# Design_Electronic_Proiect.net
KiCad netlist of a schematic drawn in EAGLE
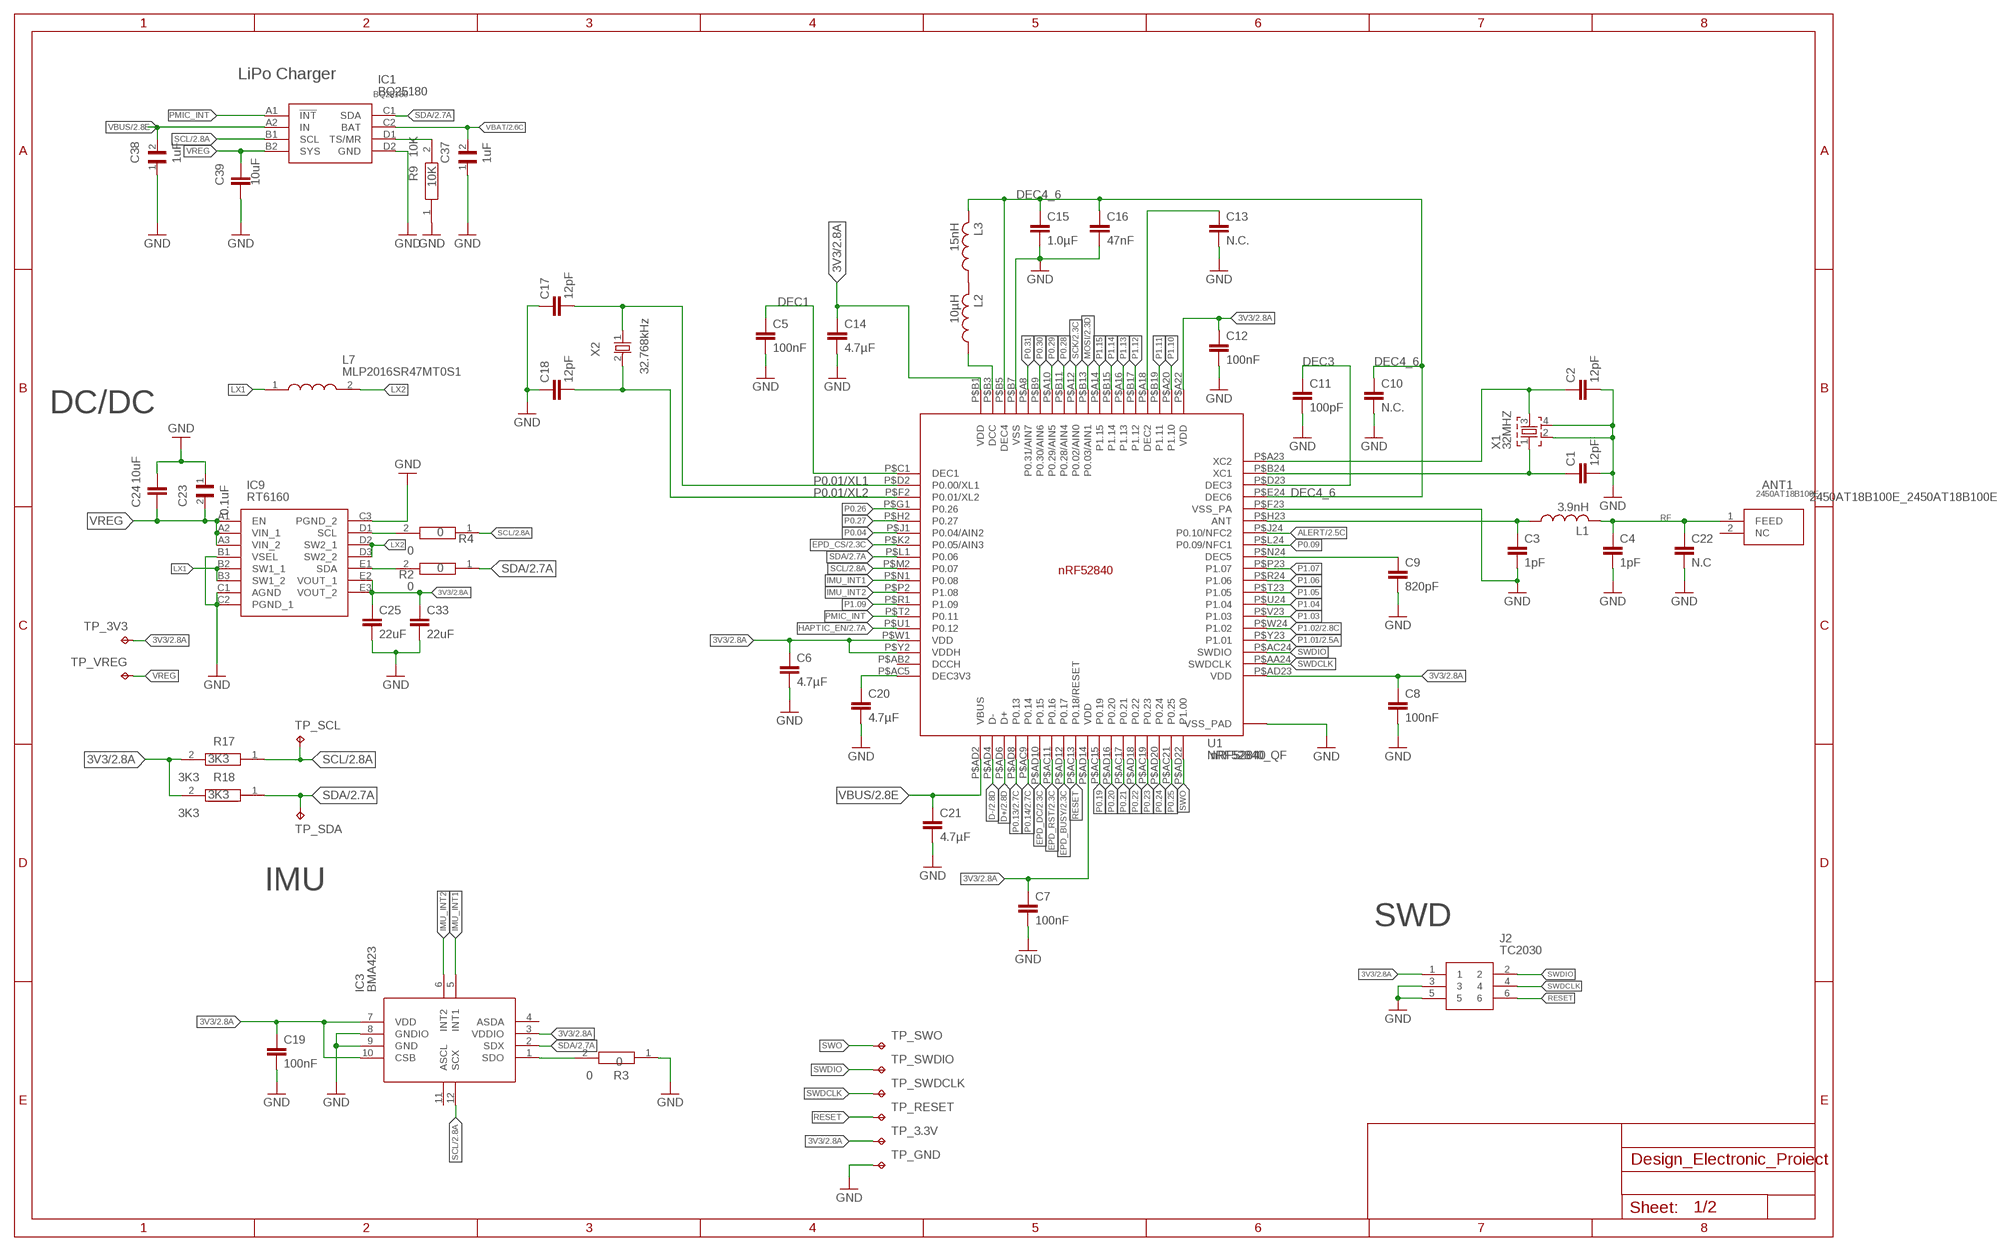
[diagram p0: schematic, sheet 1]
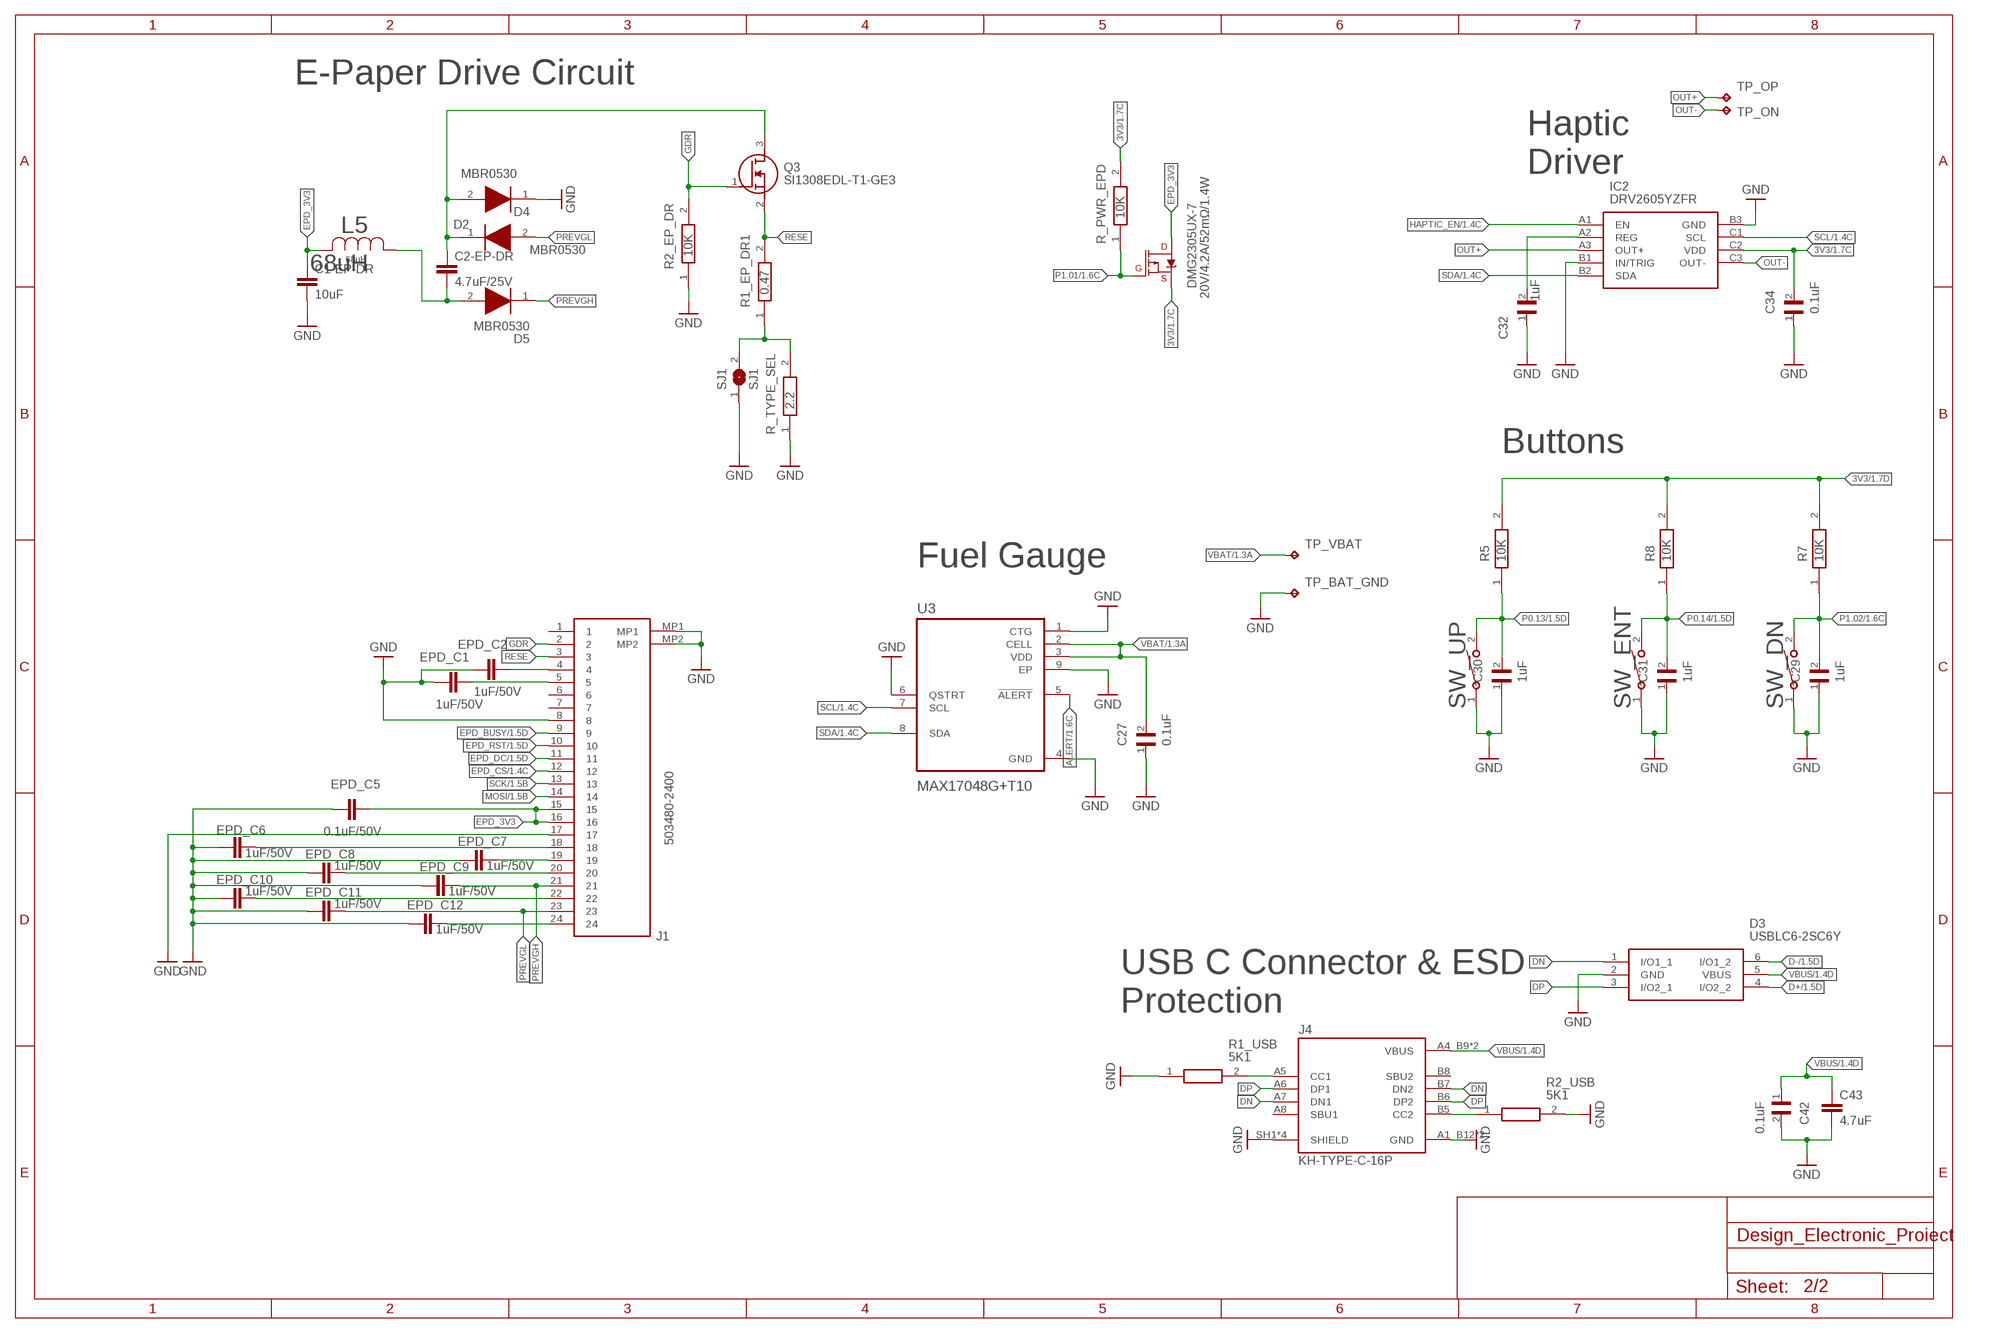
[diagram p1: schematic, sheet 2]

(export (version "E")
  (design (tool "Eeschema 10.0.6"))
  (components
    (comp (ref "ANT1")
      (value "2450AT18B100E_2450AT18B100E")
      (footprint "eagle-import:2450AT18B100E_ANTC3216X140N")
      (fields
        (field (name "ARROW_PART_NUMBER") "2450AT18B100E")
        (field (name "MOUSER_PART_NUMBER") "609-2450AT18B100E")
      )
      (libsource (lib "eagle-import") (part "2450AT18B100E_2450AT18B100E"))
    )
    (comp (ref "C1")
      (value "12pF")
      (footprint "eagle-import:NORDIC_NRF_3_RESC0201_L")
      (libsource (lib "eagle-import") (part "NORDIC_NRF_3_CAPACITOR_0201_L"))
    )
    (comp (ref "C2")
      (value "12pF")
      (footprint "eagle-import:NORDIC_NRF_3_RESC0201_L")
      (libsource (lib "eagle-import") (part "NORDIC_NRF_3_CAPACITOR_0201_L"))
    )
    (comp (ref "C3")
      (value "1pF")
      (footprint "eagle-import:NORDIC_NRF_3_RESC0201_L")
      (libsource (lib "eagle-import") (part "NORDIC_NRF_3_CAPACITOR_0201_L"))
    )
    (comp (ref "C4")
      (value "1pF")
      (footprint "eagle-import:NORDIC_NRF_3_RESC0201_L")
      (libsource (lib "eagle-import") (part "NORDIC_NRF_3_CAPACITOR_0201_L"))
    )
    (comp (ref "C5")
      (value "100nF")
      (footprint "eagle-import:NORDIC_NRF_3_RESC0201_L")
      (libsource (lib "eagle-import") (part "NORDIC_NRF_3_CAPACITOR_0201_L"))
    )
    (comp (ref "C6")
      (value "4.7µF")
      (footprint "eagle-import:NORDIC_NRF_3_RESC0201_L")
      (libsource (lib "eagle-import") (part "NORDIC_NRF_3_CAPACITOR_0201_L"))
    )
    (comp (ref "C7")
      (value "100nF")
      (footprint "eagle-import:NORDIC_NRF_3_RESC0201_L")
      (libsource (lib "eagle-import") (part "NORDIC_NRF_3_CAPACITOR_0201_L"))
    )
    (comp (ref "C8")
      (value "100nF")
      (footprint "eagle-import:NORDIC_NRF_3_RESC0201_L")
      (libsource (lib "eagle-import") (part "NORDIC_NRF_3_CAPACITOR_0201_L"))
    )
    (comp (ref "C9")
      (value "820pF")
      (footprint "eagle-import:NORDIC_NRF_3_RESC0201_L")
      (libsource (lib "eagle-import") (part "NORDIC_NRF_3_CAPACITOR_0201_L"))
    )
    (comp (ref "C10")
      (value "N.C.")
      (footprint "eagle-import:NORDIC_NRF_3_RESC0201_L")
      (libsource (lib "eagle-import") (part "NORDIC_NRF_3_CAPACITOR_0201_L"))
    )
    (comp (ref "C11")
      (value "100pF")
      (footprint "eagle-import:NORDIC_NRF_3_RESC0201_L")
      (libsource (lib "eagle-import") (part "NORDIC_NRF_3_CAPACITOR_0201_L"))
    )
    (comp (ref "C12")
      (value "100nF")
      (footprint "eagle-import:NORDIC_NRF_3_RESC0201_L")
      (libsource (lib "eagle-import") (part "NORDIC_NRF_3_CAPACITOR_0201_L"))
    )
    (comp (ref "C13")
      (value "N.C.")
      (footprint "eagle-import:NORDIC_NRF_3_RESC0201_L")
      (libsource (lib "eagle-import") (part "NORDIC_NRF_3_CAPACITOR_0201_L"))
    )
    (comp (ref "C14")
      (value "4.7µF")
      (footprint "eagle-import:NORDIC_NRF_3_RESC0201_L")
      (libsource (lib "eagle-import") (part "NORDIC_NRF_3_CAPACITOR_0201_L"))
    )
    (comp (ref "C15")
      (value "1.0µF")
      (footprint "eagle-import:NORDIC_NRF_3_RESC0201_L")
      (libsource (lib "eagle-import") (part "NORDIC_NRF_3_CAPACITOR_0201_L"))
    )
    (comp (ref "C16")
      (value "47nF")
      (footprint "eagle-import:NORDIC_NRF_3_RESC0201_L")
      (libsource (lib "eagle-import") (part "NORDIC_NRF_3_CAPACITOR_0201_L"))
    )
    (comp (ref "C17")
      (value "12pF")
      (footprint "eagle-import:NORDIC_NRF_3_RESC0201_L")
      (libsource (lib "eagle-import") (part "NORDIC_NRF_3_CAPACITOR_0201_L"))
    )
    (comp (ref "C18")
      (value "12pF")
      (footprint "eagle-import:NORDIC_NRF_3_RESC0201_L")
      (libsource (lib "eagle-import") (part "NORDIC_NRF_3_CAPACITOR_0201_L"))
    )
    (comp (ref "C19")
      (value "100nF")
      (footprint "eagle-import:NORDIC_NRF_3_RESC0402_L")
      (libsource (lib "eagle-import") (part "NORDIC_NRF_3_CAPACITOR_0402_L"))
    )
    (comp (ref "C20")
      (value "4.7µF")
      (footprint "eagle-import:NORDIC_NRF_3_RESC0201_L")
      (libsource (lib "eagle-import") (part "NORDIC_NRF_3_CAPACITOR_0201_L"))
    )
    (comp (ref "C21")
      (value "4.7µF")
      (footprint "eagle-import:NORDIC_NRF_3_RESC0201_L")
      (libsource (lib "eagle-import") (part "NORDIC_NRF_3_CAPACITOR_0201_L"))
    )
    (comp (ref "C22")
      (value "N.C")
      (footprint "eagle-import:NORDIC_NRF_3_RESC0201_L")
      (libsource (lib "eagle-import") (part "NORDIC_NRF_3_CAPACITOR_0201_L"))
    )
    (comp (ref "C23")
      (value "0.1uF")
      (footprint "eagle-import:GRM011R60J152KE01L_2_CAPC0201X13N")
      (fields (field (name "MF") "Murata") (field (name "MP") "GRM011R60J152KE01L"))
      (libsource (lib "eagle-import") (part "GRM011R60J152KE01L_2_GRM011R60J152KE01L"))
    )
    (comp (ref "C24")
      (value "10uF")
      (footprint "eagle-import:NORDIC_NRF_3_RESC0402_L")
      (libsource (lib "eagle-import") (part "NORDIC_NRF_3_CAPACITOR_0402_L"))
    )
    (comp (ref "C25")
      (value "22uF")
      (footprint "eagle-import:NORDIC_NRF_3_RESC0402_L")
      (libsource (lib "eagle-import") (part "NORDIC_NRF_3_CAPACITOR_0402_L"))
    )
    (comp (ref "C33")
      (value "22uF")
      (footprint "eagle-import:NORDIC_NRF_3_RESC0402_L")
      (libsource (lib "eagle-import") (part "NORDIC_NRF_3_CAPACITOR_0402_L"))
    )
    (comp (ref "C37")
      (value "1uF")
      (footprint "eagle-import:GRM011R60J152KE01L_2_CAPC0201X13N")
      (fields (field (name "MF") "Murata") (field (name "MP") "GRM011R60J152KE01L"))
      (libsource (lib "eagle-import") (part "GRM011R60J152KE01L_2_GRM011R60J152KE01L"))
    )
    (comp (ref "C38")
      (value "1uF")
      (footprint "eagle-import:GRM011R60J152KE01L_2_CAPC0201X13N")
      (fields (field (name "MF") "Murata") (field (name "MP") "GRM011R60J152KE01L"))
      (libsource (lib "eagle-import") (part "GRM011R60J152KE01L_2_GRM011R60J152KE01L"))
    )
    (comp (ref "C39")
      (value "10uF")
      (footprint "eagle-import:NORDIC_NRF_3_RESC0402_L")
      (libsource (lib "eagle-import") (part "NORDIC_NRF_3_CAPACITOR_0402_L"))
    )
    (comp (ref "IC1")
      (value "BQ25180")
      (footprint "eagle-import:BQ25180YBGR_BGA8C40P2X4_100X155X50")
      (fields
        (field (name "ARROW_PART_NUMBER") "BQ25180YBGR")
        (field (name "MOUSER_PART_NUMBER") "595-BQ25180YBGR")
      )
      (libsource (lib "eagle-import") (part "BQ25180YBGR_BQ25180YBGR"))
    )
    (comp (ref "IC3")
      (value "BMA423")
      (footprint "eagle-import:BMA423_BMA423")
      (fields (field (name "MOUSER_PART_NUMBER") "262-BMA423"))
      (libsource (lib "eagle-import") (part "BMA423_BMA423"))
    )
    (comp (ref "IC9")
      (value "RT6160")
      (footprint "eagle-import:RT6160AWSC_BGA15C40P3X5_140X230X60")
      (fields
        (field (name "MANUFACTURER_PART_NUMBER") "RT6160AWSC")
        (field (name "MOUSER_PART_NUMBER") "835-RT6160AWSC")
      )
      (libsource (lib "eagle-import") (part "RT6160AWSC_RT6160AWSC"))
    )
    (comp (ref "J2")
      (value "TC2030")
      (footprint "eagle-import:TC2030-IDC_TC2030IDC")
      (fields (field (name "MANUFACTURER_PART_NUMBER") "TC2030-IDC"))
      (libsource (lib "eagle-import") (part "TC2030-IDC_TC2030-IDC"))
    )
    (comp (ref "L1")
      (value "3.9nH")
      (footprint "eagle-import:NORDIC_NRF_2_RESC0402_L")
      (libsource (lib "eagle-import") (part "NORDIC_NRF_2_INDUCTOR_0402_L"))
    )
    (comp (ref "L2")
      (value "10µH")
      (footprint "eagle-import:NORDIC_NRF_2_RESC0402_L")
      (libsource (lib "eagle-import") (part "NORDIC_NRF_2_INDUCTOR_0402_L"))
    )
    (comp (ref "L3")
      (value "15nH")
      (footprint "eagle-import:NORDIC_NRF_2_RESC0402_L")
      (libsource (lib "eagle-import") (part "NORDIC_NRF_2_INDUCTOR_0402_L"))
    )
    (comp (ref "L7")
      (value "MLP2016SR47MT0S1")
      (footprint "eagle-import:MLP2016SR47MT0S1_INDC2016X100N")
      (fields (field (name "MANUFACTURER_PART_NUMBER") "FTC252012SR47MBCA"))
      (libsource (lib "eagle-import") (part "MLP2016SR47MT0S1_FTC252012SR47MBCA"))
    )
    (comp (ref "R2")
      (value "0")
      (footprint "eagle-import:CPF0201D7K68C1_0201")
      (fields (field (name "R1") "0"))
      (libsource (lib "eagle-import") (part "CPF0201D7K68C1_CPF0201D7K68C1"))
    )
    (comp (ref "R3")
      (value "0")
      (footprint "eagle-import:CPF0201D7K68C1_0201")
      (fields (field (name "R1") "0"))
      (libsource (lib "eagle-import") (part "CPF0201D7K68C1_CPF0201D7K68C1"))
    )
    (comp (ref "R4")
      (value "0")
      (footprint "eagle-import:CPF0201D7K68C1_0201")
      (fields (field (name "R1") "0"))
      (libsource (lib "eagle-import") (part "CPF0201D7K68C1_CPF0201D7K68C1"))
    )
    (comp (ref "R9")
      (value "10K")
      (footprint "eagle-import:CPF0201D7K68C1_0201")
      (fields (field (name "R1") "10K"))
      (libsource (lib "eagle-import") (part "CPF0201D7K68C1_CPF0201D7K68C1"))
    )
    (comp (ref "R17")
      (value "3K3")
      (footprint "eagle-import:CPF0201D7K68C1_0201")
      (fields (field (name "R1") "3K3"))
      (libsource (lib "eagle-import") (part "CPF0201D7K68C1_CPF0201D7K68C1"))
    )
    (comp (ref "R18")
      (value "3K3")
      (footprint "eagle-import:CPF0201D7K68C1_0201")
      (fields (field (name "R1") "3K3"))
      (libsource (lib "eagle-import") (part "CPF0201D7K68C1_CPF0201D7K68C1"))
    )
    (comp (ref "TP_3.3V")
      (value "HECTOR_WATCH_1_TPTP20R")
      (footprint "eagle-import:HECTOR_WATCH_1_TP20R")
      (libsource (lib "eagle-import") (part "HECTOR_WATCH_1_TPTP20R"))
    )
    (comp (ref "TP_3V3")
      (value "HECTOR_WATCH_1_TPTP20R")
      (footprint "eagle-import:HECTOR_WATCH_1_TP20R")
      (libsource (lib "eagle-import") (part "HECTOR_WATCH_1_TPTP20R"))
    )
    (comp (ref "TP_GND")
      (value "HECTOR_WATCH_1_TPTP20R")
      (footprint "eagle-import:HECTOR_WATCH_1_TP20R")
      (libsource (lib "eagle-import") (part "HECTOR_WATCH_1_TPTP20R"))
    )
    (comp (ref "TP_RESET")
      (value "HECTOR_WATCH_1_TPTP20R")
      (footprint "eagle-import:HECTOR_WATCH_1_TP20R")
      (libsource (lib "eagle-import") (part "HECTOR_WATCH_1_TPTP20R"))
    )
    (comp (ref "TP_SCL")
      (value "HECTOR_WATCH_1_TPTP20R")
      (footprint "eagle-import:HECTOR_WATCH_1_TP20R")
      (libsource (lib "eagle-import") (part "HECTOR_WATCH_1_TPTP20R"))
    )
    (comp (ref "TP_SDA")
      (value "HECTOR_WATCH_1_TPTP20R")
      (footprint "eagle-import:HECTOR_WATCH_1_TP20R")
      (libsource (lib "eagle-import") (part "HECTOR_WATCH_1_TPTP20R"))
    )
    (comp (ref "TP_SWDCLK")
      (value "HECTOR_WATCH_1_TPTP20R")
      (footprint "eagle-import:HECTOR_WATCH_1_TP20R")
      (libsource (lib "eagle-import") (part "HECTOR_WATCH_1_TPTP20R"))
    )
    (comp (ref "TP_SWDIO")
      (value "HECTOR_WATCH_1_TPTP20R")
      (footprint "eagle-import:HECTOR_WATCH_1_TP20R")
      (libsource (lib "eagle-import") (part "HECTOR_WATCH_1_TPTP20R"))
    )
    (comp (ref "TP_SWO")
      (value "HECTOR_WATCH_1_TPTP20R")
      (footprint "eagle-import:HECTOR_WATCH_1_TP20R")
      (libsource (lib "eagle-import") (part "HECTOR_WATCH_1_TPTP20R"))
    )
    (comp (ref "TP_VREG")
      (value "HECTOR_WATCH_1_TPTP20R")
      (footprint "eagle-import:HECTOR_WATCH_1_TP20R")
      (libsource (lib "eagle-import") (part "HECTOR_WATCH_1_TPTP20R"))
    )
    (comp (ref "U1")
      (value "nRF52840")
      (footprint "eagle-import:NORDIC_NRF_4_AQFN50P700X700X85_HS-74N")
      (libsource (lib "eagle-import") (part "NORDIC_NRF_4_NRF52840_QF"))
    )
    (comp (ref "X1")
      (value "32MHZ")
      (footprint "eagle-import:NORDIC_NRF_BT-XTAL_2016_N")
      (libsource (lib "eagle-import") (part "NORDIC_NRF_XTAL_32MHZ"))
    )
    (comp (ref "X2")
      (value "32.768kHz")
      (footprint "eagle-import:NORDIC_NRF_1_XTAL_3215_N")
      (libsource (lib "eagle-import") (part "NORDIC_NRF_1_XTAL_32KHZ"))
    )
    (comp (ref "C1-EP-DR")
      (value "10uF")
      (footprint "eagle-import:NORDIC_NRF_3_RESC0402_L")
      (libsource (lib "eagle-import") (part "NORDIC_NRF_3_CAPACITOR_0402_L"))
    )
    (comp (ref "C2-EP-DR")
      (value "4.7uF/25V")
      (footprint "eagle-import:NORDIC_NRF_3_RESC0402_L")
      (libsource (lib "eagle-import") (part "NORDIC_NRF_3_CAPACITOR_0402_L"))
    )
    (comp (ref "C27")
      (value "0.1uF")
      (footprint "eagle-import:GRM011R60J152KE01L_2_CAPC0201X13N")
      (fields (field (name "MF") "Murata") (field (name "MP") "GRM011R60J152KE01L"))
      (libsource (lib "eagle-import") (part "GRM011R60J152KE01L_2_GRM011R60J152KE01L"))
    )
    (comp (ref "C29")
      (value "1uF")
      (footprint "eagle-import:GRM011R60J152KE01L_2_CAPC0201X13N")
      (fields (field (name "MF") "Murata") (field (name "MP") "GRM011R60J152KE01L"))
      (libsource (lib "eagle-import") (part "GRM011R60J152KE01L_2_GRM011R60J152KE01L"))
    )
    (comp (ref "C30")
      (value "1uF")
      (footprint "eagle-import:GRM011R60J152KE01L_2_CAPC0201X13N")
      (fields (field (name "MF") "Murata") (field (name "MP") "GRM011R60J152KE01L"))
      (libsource (lib "eagle-import") (part "GRM011R60J152KE01L_2_GRM011R60J152KE01L"))
    )
    (comp (ref "C31")
      (value "1uF")
      (footprint "eagle-import:GRM011R60J152KE01L_2_CAPC0201X13N")
      (fields (field (name "MF") "Murata") (field (name "MP") "GRM011R60J152KE01L"))
      (libsource (lib "eagle-import") (part "GRM011R60J152KE01L_2_GRM011R60J152KE01L"))
    )
    (comp (ref "C32")
      (value "1uF")
      (footprint "eagle-import:GRM011R60J152KE01L_2_CAPC0201X13N")
      (fields (field (name "MF") "Murata") (field (name "MP") "GRM011R60J152KE01L"))
      (libsource (lib "eagle-import") (part "GRM011R60J152KE01L_2_GRM011R60J152KE01L"))
    )
    (comp (ref "C34")
      (value "0.1uF")
      (footprint "eagle-import:GRM011R60J152KE01L_2_CAPC0201X13N")
      (fields (field (name "MF") "Murata") (field (name "MP") "GRM011R60J152KE01L"))
      (libsource (lib "eagle-import") (part "GRM011R60J152KE01L_2_GRM011R60J152KE01L"))
    )
    (comp (ref "C42")
      (value "0.1uF")
      (footprint "eagle-import:GRM011R60J152KE01L_2_CAPC0201X13N")
      (fields (field (name "MF") "Murata") (field (name "MP") "GRM011R60J152KE01L"))
      (libsource (lib "eagle-import") (part "GRM011R60J152KE01L_2_GRM011R60J152KE01L"))
    )
    (comp (ref "C43")
      (value "4.7uF")
      (footprint "eagle-import:NORDIC_NRF_3_RESC0402_L")
      (libsource (lib "eagle-import") (part "NORDIC_NRF_3_CAPACITOR_0402_L"))
    )
    (comp (ref "D2")
      (value "MBR0530")
      (footprint "eagle-import:ESP32_C6_LIBRARY_5_SOD3716X135N")
      (fields (field (name "MF") "ON Semiconductor"))
      (libsource (lib "eagle-import") (part "ESP32_C6_LIBRARY_5_MBR0530"))
    )
    (comp (ref "D3")
      (value "USBLC6-2SC6Y")
      (footprint "eagle-import:ESP32_C6_LIBRARY_3_SOT95P280X145-6N")
      (fields (field (name "MF") "STMicroelectronics"))
      (libsource (lib "eagle-import") (part "ESP32_C6_LIBRARY_3_USBLC6-2SC6Y"))
    )
    (comp (ref "D4")
      (value "MBR0530")
      (footprint "eagle-import:ESP32_C6_LIBRARY_5_SOD3716X135N")
      (fields (field (name "MF") "ON Semiconductor"))
      (libsource (lib "eagle-import") (part "ESP32_C6_LIBRARY_5_MBR0530"))
    )
    (comp (ref "D5")
      (value "MBR0530")
      (footprint "eagle-import:ESP32_C6_LIBRARY_5_SOD3716X135N")
      (fields (field (name "MF") "ON Semiconductor"))
      (libsource (lib "eagle-import") (part "ESP32_C6_LIBRARY_5_MBR0530"))
    )
    (comp (ref "DMG2305UX-7")
      (value "20V/4.2A/52mΩ/1.4W")
      (footprint "eagle-import:ESP32_C6_LIBRARY_4_ESP32_C6_LIBRARY_4_ESP32_C6_LIBRARY_4_ESP32_C6_LIBRARY_4_ESP32_WROVER_SPARKFUN-DISCRETESEMI_SOT23-3")
      (libsource (lib "eagle-import") (part "ESP32_C6_LIBRARY_4_ESP32_WROVER_SPARKFUN-DISCRETESEMI_MOSFET_PCH-DMG2305UX-7"))
    )
    (comp (ref "EPD_C1")
      (value "1uF/50V")
      (footprint "eagle-import:NORDIC_NRF_3_RESC0402_L")
      (libsource (lib "eagle-import") (part "NORDIC_NRF_3_CAPACITOR_0402_L"))
    )
    (comp (ref "EPD_C2")
      (value "1uF/50V")
      (footprint "eagle-import:NORDIC_NRF_3_RESC0402_L")
      (libsource (lib "eagle-import") (part "NORDIC_NRF_3_CAPACITOR_0402_L"))
    )
    (comp (ref "EPD_C5")
      (value "0.1uF/50V")
      (footprint "eagle-import:NORDIC_NRF_3_RESC0402_L")
      (libsource (lib "eagle-import") (part "NORDIC_NRF_3_CAPACITOR_0402_L"))
    )
    (comp (ref "EPD_C6")
      (value "1uF/50V")
      (footprint "eagle-import:NORDIC_NRF_3_RESC0402_L")
      (libsource (lib "eagle-import") (part "NORDIC_NRF_3_CAPACITOR_0402_L"))
    )
    (comp (ref "EPD_C7")
      (value "1uF/50V")
      (footprint "eagle-import:NORDIC_NRF_3_RESC0402_L")
      (libsource (lib "eagle-import") (part "NORDIC_NRF_3_CAPACITOR_0402_L"))
    )
    (comp (ref "EPD_C8")
      (value "1uF/50V")
      (footprint "eagle-import:NORDIC_NRF_3_RESC0402_L")
      (libsource (lib "eagle-import") (part "NORDIC_NRF_3_CAPACITOR_0402_L"))
    )
    (comp (ref "EPD_C9")
      (value "1uF/50V")
      (footprint "eagle-import:NORDIC_NRF_3_RESC0402_L")
      (libsource (lib "eagle-import") (part "NORDIC_NRF_3_CAPACITOR_0402_L"))
    )
    (comp (ref "EPD_C10")
      (value "1uF/50V")
      (footprint "eagle-import:NORDIC_NRF_3_RESC0402_L")
      (libsource (lib "eagle-import") (part "NORDIC_NRF_3_CAPACITOR_0402_L"))
    )
    (comp (ref "EPD_C11")
      (value "1uF/50V")
      (footprint "eagle-import:NORDIC_NRF_3_RESC0402_L")
      (libsource (lib "eagle-import") (part "NORDIC_NRF_3_CAPACITOR_0402_L"))
    )
    (comp (ref "EPD_C12")
      (value "1uF/50V")
      (footprint "eagle-import:NORDIC_NRF_3_RESC0402_L")
      (libsource (lib "eagle-import") (part "NORDIC_NRF_3_CAPACITOR_0402_L"))
    )
    (comp (ref "IC2")
      (value "DRV2605YZFR")
      (footprint "eagle-import:DRV2605YZFR_BGA9C50P3X3_144X144X62")
      (libsource (lib "eagle-import") (part "DRV2605YZFR_DRV2605YZFR"))
    )
    (comp (ref "J1")
      (value "503480-2400")
      (footprint "eagle-import:503480-2400_5034802400")
      (fields (field (name "MOUSER_PART_NUMBER") "538-503480-2400"))
      (libsource (lib "eagle-import") (part "503480-2400_503480-2400"))
    )
    (comp (ref "J4")
      (value "KH-TYPE-C-16P")
      (footprint "eagle-import:KH-TYPE-C-16P_KINGHELM_KH-TYPE-C-16P")
      (fields (field (name "MF") "kinghelm"))
      (libsource (lib "eagle-import") (part "KH-TYPE-C-16P_KH-TYPE-C-16P"))
    )
    (comp (ref "L5")
      (value "68uH")
      (footprint "eagle-import:ESP32_C6_LIBRARY_2_IND_4828-WE-TPC_WRE")
      (fields
        (field (name "MANUFACTURER_PART_NUMBER") "744043680")
        (field (name "SHOW_VALUE") "68uH")
        (field (name "COPYRIGHT") "Copyright (C) 2024 Ultra Librarian. All rights reserved.")
      )
      (libsource (lib "eagle-import") (part "ESP32_C6_LIBRARY_2_744043680IND_4828-WE-TPC_WRE"))
    )
    (comp (ref "Q3")
      (value "SI1308EDL-T1-GE3")
      (footprint "eagle-import:ESP32_C6_LIBRARY_6_SOT65P210X110-3N")
      (fields (field (name "MF") "Vishay Siliconix"))
      (libsource (lib "eagle-import") (part "ESP32_C6_LIBRARY_6_SI1308EDL-T1-GE3"))
    )
    (comp (ref "R1_EP_DR1")
      (value "0.47")
      (footprint "eagle-import:CPF0201D7K68C1_0201")
      (libsource (lib "eagle-import") (part "CPF0201D7K68C1_CPF0201D7K68C1"))
    )
    (comp (ref "R1_USB")
      (value "5K1")
      (footprint "eagle-import:CPF0201D7K68C1_0201")
      (libsource (lib "eagle-import") (part "CPF0201D7K68C1_CPF0201D7K68C1"))
    )
    (comp (ref "R2_EP_DR")
      (value "10K")
      (footprint "eagle-import:CPF0201D7K68C1_0201")
      (libsource (lib "eagle-import") (part "CPF0201D7K68C1_CPF0201D7K68C1"))
    )
    (comp (ref "R2_USB")
      (value "5K1")
      (footprint "eagle-import:CPF0201D7K68C1_0201")
      (libsource (lib "eagle-import") (part "CPF0201D7K68C1_CPF0201D7K68C1"))
    )
    (comp (ref "R5")
      (value "10K")
      (footprint "eagle-import:CPF0201D7K68C1_0201")
      (libsource (lib "eagle-import") (part "CPF0201D7K68C1_CPF0201D7K68C1"))
    )
    (comp (ref "R7")
      (value "10K")
      (footprint "eagle-import:CPF0201D7K68C1_0201")
      (libsource (lib "eagle-import") (part "CPF0201D7K68C1_CPF0201D7K68C1"))
    )
    (comp (ref "R8")
      (value "10K")
      (footprint "eagle-import:CPF0201D7K68C1_0201")
      (libsource (lib "eagle-import") (part "CPF0201D7K68C1_CPF0201D7K68C1"))
    )
    (comp (ref "R_PWR_EPD")
      (value "10K")
      (footprint "eagle-import:CPF0201D7K68C1_0201")
      (libsource (lib "eagle-import") (part "CPF0201D7K68C1_CPF0201D7K68C1"))
    )
    (comp (ref "R_TYPE_SEL")
      (value "2.2")
      (footprint "eagle-import:CPF0201D7K68C1_0201")
      (libsource (lib "eagle-import") (part "CPF0201D7K68C1_CPF0201D7K68C1"))
    )
    (comp (ref "SJ1")
      (value "SJ1")
      (footprint "eagle-import:ESP32_C6_LIBRARY_7_JUMPER_SJ")
      (libsource (lib "eagle-import") (part "ESP32_C6_LIBRARY_7_JUMPER_SJ"))
    )
    (comp (ref "SW_DN")
      (value "2025-10-22_07-23-44_LIBRARY_EVP-AKE31ASW_EVP-AKE31A_PAN")
      (footprint "eagle-import:2025-10-22_07-23-44_LIBRARY_SW_EVP-AKE31A_PAN")
      (fields
        (field (name "MANUFACTURER_PART_NUMBER") "EVP-AKE31A")
        (field (name "COPYRIGHT") "Copyright (C) 2025 Ultra Librarian. All rights reserved.")
      )
      (libsource (lib "eagle-import") (part "2025-10-22_07-23-44_LIBRARY_EVP-AKE31ASW_EVP-AKE31A_PAN"))
    )
    (comp (ref "SW_ENT")
      (value "2025-10-22_07-23-44_LIBRARY_EVP-AKE31ASW_EVP-AKE31A_PAN")
      (footprint "eagle-import:2025-10-22_07-23-44_LIBRARY_SW_EVP-AKE31A_PAN")
      (fields
        (field (name "MANUFACTURER_PART_NUMBER") "EVP-AKE31A")
        (field (name "COPYRIGHT") "Copyright (C) 2025 Ultra Librarian. All rights reserved.")
      )
      (libsource (lib "eagle-import") (part "2025-10-22_07-23-44_LIBRARY_EVP-AKE31ASW_EVP-AKE31A_PAN"))
    )
    (comp (ref "SW_UP")
      (value "2025-10-22_07-23-44_LIBRARY_EVP-AKE31ASW_EVP-AKE31A_PAN")
      (footprint "eagle-import:2025-10-22_07-23-44_LIBRARY_SW_EVP-AKE31A_PAN")
      (fields
        (field (name "MANUFACTURER_PART_NUMBER") "EVP-AKE31A")
        (field (name "COPYRIGHT") "Copyright (C) 2025 Ultra Librarian. All rights reserved.")
      )
      (libsource (lib "eagle-import") (part "2025-10-22_07-23-44_LIBRARY_EVP-AKE31ASW_EVP-AKE31A_PAN"))
    )
    (comp (ref "TP_BAT_GND")
      (value "HECTOR_WATCH_1_TPTP20R")
      (footprint "eagle-import:HECTOR_WATCH_1_TP20R")
      (libsource (lib "eagle-import") (part "HECTOR_WATCH_1_TPTP20R"))
    )
    (comp (ref "TP_ON")
      (value "HECTOR_WATCH_1_TPTP20R")
      (footprint "eagle-import:HECTOR_WATCH_1_TP20R")
      (libsource (lib "eagle-import") (part "HECTOR_WATCH_1_TPTP20R"))
    )
    (comp (ref "TP_OP")
      (value "HECTOR_WATCH_1_TPTP20R")
      (footprint "eagle-import:HECTOR_WATCH_1_TP20R")
      (libsource (lib "eagle-import") (part "HECTOR_WATCH_1_TPTP20R"))
    )
    (comp (ref "TP_VBAT")
      (value "HECTOR_WATCH_1_TPTP20R")
      (footprint "eagle-import:HECTOR_WATCH_1_TP20R")
      (libsource (lib "eagle-import") (part "HECTOR_WATCH_1_TPTP20R"))
    )
    (comp (ref "U3")
      (value "MAX17048G+T10")
      (footprint "eagle-import:ESP32_C6_LIBRARY_SON50P200X200X80-9N")
      (fields (field (name "MF") "Analog Devices"))
      (libsource (lib "eagle-import") (part "ESP32_C6_LIBRARY_MAX17048G+T10"))
    )
  )
  (nets
    (net (code "1") (name "3V3") (class "Default")
      (node (ref "C12") (pin "1") (pinfunction "1_1") (pintype "passive"))
      (node (ref "C14") (pin "1") (pinfunction "1_1") (pintype "passive"))
      (node (ref "C19") (pin "1") (pinfunction "1_1") (pintype "passive"))
      (node (ref "C25") (pin "1") (pinfunction "1_1") (pintype "passive"))
      (node (ref "C33") (pin "1") (pinfunction "1_1") (pintype "passive"))
      (node (ref "C34") (pin "2") (pinfunction "2_2") (pintype "passive"))
      (node (ref "C6") (pin "1") (pinfunction "1_1") (pintype "passive"))
      (node (ref "C7") (pin "1") (pinfunction "1_1") (pintype "passive"))
      (node (ref "C8") (pin "1") (pinfunction "1_1") (pintype "passive"))
      (node (ref "DMG2305UX-7") (pin "2") (pinfunction "S_2") (pintype "bidirectional"))
      (node (ref "IC2") (pin "C2") (pinfunction "VDD_C2") (pintype "bidirectional"))
      (node (ref "IC3") (pin "10") (pinfunction "CSB_10") (pintype "bidirectional"))
      (node (ref "IC3") (pin "3") (pinfunction "VDDIO_3") (pintype "bidirectional"))
      (node (ref "IC3") (pin "7") (pinfunction "VDD_7") (pintype "bidirectional"))
      (node (ref "IC9") (pin "E2") (pinfunction "VOUT_1_E2") (pintype "bidirectional"))
      (node (ref "IC9") (pin "E3") (pinfunction "VOUT_2_E3") (pintype "bidirectional"))
      (node (ref "J2") (pin "1") (pinfunction "1_1") (pintype "bidirectional"))
      (node (ref "R17") (pin "2") (pinfunction "2_2") (pintype "bidirectional"))
      (node (ref "R18") (pin "2") (pinfunction "2_2") (pintype "bidirectional"))
      (node (ref "R_PWR_EPD") (pin "2") (pinfunction "2_2") (pintype "bidirectional"))
      (node (ref "TP_3.3V") (pin "TP") (pinfunction "TP_TP") (pintype "input"))
      (node (ref "TP_3V3") (pin "TP") (pinfunction "TP_TP") (pintype "input"))
      (node (ref "U1") (pin "P$A22") (pinfunction "VDD_P$A22") (pintype "power_in"))
      (node (ref "U1") (pin "P$AD14") (pinfunction "VDD_P$AD14") (pintype "power_in"))
      (node (ref "U1") (pin "P$AD23") (pinfunction "VDD_P$AD23") (pintype "power_in"))
      (node (ref "U1") (pin "P$B1") (pinfunction "VDD_P$B1") (pintype "power_in"))
      (node (ref "U1") (pin "P$W1") (pinfunction "VDD_P$W1") (pintype "power_in"))
      (node (ref "U1") (pin "P$Y2") (pinfunction "VDDH_P$Y2") (pintype "power_in"))
    )
    (net (code "2") (name "3V3{slash}1.7D") (class "Default")
      (node (ref "R5") (pin "2") (pinfunction "2_2") (pintype "bidirectional"))
      (node (ref "R7") (pin "2") (pinfunction "2_2") (pintype "bidirectional"))
      (node (ref "R8") (pin "2") (pinfunction "2_2") (pintype "bidirectional"))
    )
    (net (code "3") (name "ALERT") (class "Default")
      (node (ref "U1") (pin "P$J24") (pinfunction "P0.10/NFC2_P$J24") (pintype "bidirectional"))
      (node (ref "U3") (pin "5") (pinfunction "~{ALERT}_5") (pintype "output"))
    )
    (net (code "4") (name "D+") (class "Default")
      (node (ref "D3") (pin "4") (pinfunction "I/O2_2_4") (pintype "bidirectional"))
      (node (ref "U1") (pin "P$AD6") (pinfunction "D+_P$AD6") (pintype "bidirectional"))
    )
    (net (code "5") (name "D-") (class "Default")
      (node (ref "D3") (pin "6") (pinfunction "I/O1_2_6") (pintype "bidirectional"))
      (node (ref "U1") (pin "P$AD4") (pinfunction "D-_P$AD4") (pintype "bidirectional"))
    )
    (net (code "6") (name "DEC1") (class "Default")
      (node (ref "C5") (pin "1") (pinfunction "1_1") (pintype "passive"))
      (node (ref "U1") (pin "P$C1") (pinfunction "DEC1_P$C1") (pintype "power_in"))
    )
    (net (code "7") (name "DEC3") (class "Default")
      (node (ref "C11") (pin "1") (pinfunction "1_1") (pintype "passive"))
      (node (ref "U1") (pin "P$D23") (pinfunction "DEC3_P$D23") (pintype "bidirectional"))
    )
    (net (code "8") (name "DEC4_6") (class "Default")
      (node (ref "C10") (pin "1") (pinfunction "1_1") (pintype "passive"))
      (node (ref "C15") (pin "1") (pinfunction "1_1") (pintype "passive"))
      (node (ref "C16") (pin "1") (pinfunction "1_1") (pintype "passive"))
      (node (ref "L3") (pin "2") (pinfunction "2_2") (pintype "passive"))
      (node (ref "U1") (pin "P$B5") (pinfunction "DEC4_P$B5") (pintype "power_in"))
      (node (ref "U1") (pin "P$E24") (pinfunction "DEC6_P$E24") (pintype "bidirectional"))
    )
    (net (code "9") (name "DN") (class "Default")
      (node (ref "D3") (pin "1") (pinfunction "I/O1_1_1") (pintype "bidirectional"))
      (node (ref "J4") (pin "A7") (pinfunction "DN1_A7") (pintype "bidirectional"))
      (node (ref "J4") (pin "B7") (pinfunction "DN2_B7") (pintype "bidirectional"))
    )
    (net (code "10") (name "DP") (class "Default")
      (node (ref "D3") (pin "3") (pinfunction "I/O2_1_3") (pintype "bidirectional"))
      (node (ref "J4") (pin "A6") (pinfunction "DP1_A6") (pintype "bidirectional"))
      (node (ref "J4") (pin "B6") (pinfunction "DP2_B6") (pintype "bidirectional"))
    )
    (net (code "11") (name "EPD_3V3") (class "Default")
      (node (ref "C1-EP-DR") (pin "1") (pinfunction "1_1") (pintype "passive"))
      (node (ref "DMG2305UX-7") (pin "3") (pinfunction "D_3") (pintype "bidirectional"))
      (node (ref "EPD_C5") (pin "2") (pinfunction "2_2") (pintype "passive"))
      (node (ref "J1") (pin "15") (pinfunction "15_15") (pintype "bidirectional"))
      (node (ref "J1") (pin "16") (pinfunction "16_16") (pintype "bidirectional"))
      (node (ref "L5") (pin "2") (pinfunction "2_2") (pintype "passive"))
    )
    (net (code "12") (name "EPD_BUSY") (class "Default")
      (node (ref "J1") (pin "9") (pinfunction "9_9") (pintype "bidirectional"))
      (node (ref "U1") (pin "P$AD12") (pinfunction "P0.17_P$AD12") (pintype "bidirectional"))
    )
    (net (code "13") (name "EPD_CS") (class "Default")
      (node (ref "J1") (pin "12") (pinfunction "12_12") (pintype "bidirectional"))
      (node (ref "U1") (pin "P$K2") (pinfunction "P0.05/AIN3_P$K2") (pintype "bidirectional"))
    )
    (net (code "14") (name "EPD_DC") (class "Default")
      (node (ref "J1") (pin "11") (pinfunction "11_11") (pintype "bidirectional"))
      (node (ref "U1") (pin "P$AD10") (pinfunction "P0.15_P$AD10") (pintype "bidirectional"))
    )
    (net (code "15") (name "EPD_RST") (class "Default")
      (node (ref "J1") (pin "10") (pinfunction "10_10") (pintype "bidirectional"))
      (node (ref "U1") (pin "P$AC11") (pinfunction "P0.16_P$AC11") (pintype "bidirectional"))
    )
    (net (code "16") (name "GDR") (class "Default")
      (node (ref "J1") (pin "2") (pinfunction "2_2") (pintype "bidirectional"))
      (node (ref "Q3") (pin "1") (pinfunction "G_1") (pintype "bidirectional"))
      (node (ref "R2_EP_DR") (pin "2") (pinfunction "2_2") (pintype "bidirectional"))
    )
    (net (code "17") (name "GND") (class "Default")
      (node (ref "C1") (pin "2") (pinfunction "2_2") (pintype "passive"))
      (node (ref "C1-EP-DR") (pin "2") (pinfunction "2_2") (pintype "passive"))
      (node (ref "C10") (pin "2") (pinfunction "2_2") (pintype "passive"))
      (node (ref "C11") (pin "2") (pinfunction "2_2") (pintype "passive"))
      (node (ref "C12") (pin "2") (pinfunction "2_2") (pintype "passive"))
      (node (ref "C13") (pin "2") (pinfunction "2_2") (pintype "passive"))
      (node (ref "C14") (pin "2") (pinfunction "2_2") (pintype "passive"))
      (node (ref "C15") (pin "2") (pinfunction "2_2") (pintype "passive"))
      (node (ref "C16") (pin "2") (pinfunction "2_2") (pintype "passive"))
      (node (ref "C17") (pin "1") (pinfunction "1_1") (pintype "passive"))
      (node (ref "C18") (pin "1") (pinfunction "1_1") (pintype "passive"))
      (node (ref "C19") (pin "2") (pinfunction "2_2") (pintype "passive"))
      (node (ref "C2") (pin "2") (pinfunction "2_2") (pintype "passive"))
      (node (ref "C20") (pin "2") (pinfunction "2_2") (pintype "passive"))
      (node (ref "C21") (pin "2") (pinfunction "2_2") (pintype "passive"))
      (node (ref "C22") (pin "2") (pinfunction "2_2") (pintype "passive"))
      (node (ref "C23") (pin "1") (pinfunction "1_1") (pintype "passive"))
      (node (ref "C24") (pin "1") (pinfunction "1_1") (pintype "passive"))
      (node (ref "C25") (pin "2") (pinfunction "2_2") (pintype "passive"))
      (node (ref "C27") (pin "1") (pinfunction "1_1") (pintype "passive"))
      (node (ref "C29") (pin "1") (pinfunction "1_1") (pintype "passive"))
      (node (ref "C3") (pin "2") (pinfunction "2_2") (pintype "passive"))
      (node (ref "C30") (pin "1") (pinfunction "1_1") (pintype "passive"))
      (node (ref "C31") (pin "1") (pinfunction "1_1") (pintype "passive"))
      (node (ref "C32") (pin "1") (pinfunction "1_1") (pintype "passive"))
      (node (ref "C33") (pin "2") (pinfunction "2_2") (pintype "passive"))
      (node (ref "C34") (pin "1") (pinfunction "1_1") (pintype "passive"))
      (node (ref "C37") (pin "1") (pinfunction "1_1") (pintype "passive"))
      (node (ref "C38") (pin "1") (pinfunction "1_1") (pintype "passive"))
      (node (ref "C39") (pin "2") (pinfunction "2_2") (pintype "passive"))
      (node (ref "C4") (pin "2") (pinfunction "2_2") (pintype "passive"))
      (node (ref "C42") (pin "2") (pinfunction "2_2") (pintype "passive"))
      (node (ref "C43") (pin "2") (pinfunction "2_2") (pintype "passive"))
      (node (ref "C5") (pin "2") (pinfunction "2_2") (pintype "passive"))
      (node (ref "C6") (pin "2") (pinfunction "2_2") (pintype "passive"))
      (node (ref "C7") (pin "2") (pinfunction "2_2") (pintype "passive"))
      (node (ref "C8") (pin "2") (pinfunction "2_2") (pintype "passive"))
      (node (ref "C9") (pin "2") (pinfunction "2_2") (pintype "passive"))
      (node (ref "D3") (pin "2") (pinfunction "GND_2") (pintype "bidirectional"))
      (node (ref "D4") (pin "1") (pinfunction "K_1") (pintype "bidirectional"))
      (node (ref "EPD_C1") (pin "1") (pinfunction "1_1") (pintype "passive"))
      (node (ref "EPD_C10") (pin "1") (pinfunction "1_1") (pintype "passive"))
      (node (ref "EPD_C11") (pin "1") (pinfunction "1_1") (pintype "passive"))
      (node (ref "EPD_C12") (pin "1") (pinfunction "1_1") (pintype "passive"))
      (node (ref "EPD_C2") (pin "1") (pinfunction "1_1") (pintype "passive"))
      (node (ref "EPD_C5") (pin "1") (pinfunction "1_1") (pintype "passive"))
      (node (ref "EPD_C6") (pin "1") (pinfunction "1_1") (pintype "passive"))
      (node (ref "EPD_C7") (pin "1") (pinfunction "1_1") (pintype "passive"))
      (node (ref "EPD_C8") (pin "1") (pinfunction "1_1") (pintype "passive"))
      (node (ref "EPD_C9") (pin "1") (pinfunction "1_1") (pintype "passive"))
      (node (ref "IC1") (pin "D2") (pinfunction "GND_D2") (pintype "bidirectional"))
      (node (ref "IC2") (pin "B1") (pinfunction "IN/TRIG_B1") (pintype "bidirectional"))
      (node (ref "IC2") (pin "B3") (pinfunction "GND_B3") (pintype "bidirectional"))
      (node (ref "IC3") (pin "8") (pinfunction "GNDIO_8") (pintype "bidirectional"))
      (node (ref "IC3") (pin "9") (pinfunction "GND_9") (pintype "bidirectional"))
      (node (ref "IC9") (pin "B1") (pinfunction "VSEL_B1") (pintype "bidirectional"))
      (node (ref "IC9") (pin "C1") (pinfunction "AGND_C1") (pintype "bidirectional"))
      (node (ref "IC9") (pin "C2") (pinfunction "PGND_1_C2") (pintype "bidirectional"))
      (node (ref "IC9") (pin "C3") (pinfunction "PGND_2_C3") (pintype "bidirectional"))
      (node (ref "J1") (pin "17") (pinfunction "17_17") (pintype "bidirectional"))
      (node (ref "J1") (pin "8") (pinfunction "8_8") (pintype "bidirectional"))
      (node (ref "J1") (pin "MP1") (pinfunction "MP1_MP1") (pintype "bidirectional"))
      (node (ref "J1") (pin "MP2") (pinfunction "MP2_MP2") (pintype "bidirectional"))
      (node (ref "J2") (pin "3") (pinfunction "3_3") (pintype "bidirectional"))
      (node (ref "J2") (pin "5") (pinfunction "5_5") (pintype "bidirectional"))
      (node (ref "J4") (pin "A12_B1") (pinfunction "GND_A12_B1") (pintype "power_in"))
      (node (ref "J4") (pin "A1_B12") (pinfunction "GND_A1_B12") (pintype "power_in"))
      (node (ref "J4") (pin "SH1") (pinfunction "SHIELD_SH1") (pintype "passive"))
      (node (ref "J4") (pin "SH2") (pinfunction "SHIELD_SH2") (pintype "passive"))
      (node (ref "J4") (pin "SH3") (pinfunction "SHIELD_SH3") (pintype "passive"))
      (node (ref "J4") (pin "SH4") (pinfunction "SHIELD_SH4") (pintype "passive"))
      (node (ref "R1_USB") (pin "1") (pinfunction "1_1") (pintype "bidirectional"))
      (node (ref "R2_EP_DR") (pin "1") (pinfunction "1_1") (pintype "bidirectional"))
      (node (ref "R2_USB") (pin "2") (pinfunction "2_2") (pintype "bidirectional"))
      (node (ref "R3") (pin "1") (pinfunction "1_1") (pintype "bidirectional"))
      (node (ref "R9") (pin "1") (pinfunction "1_1") (pintype "bidirectional"))
      (node (ref "R_TYPE_SEL") (pin "1") (pinfunction "1_1") (pintype "bidirectional"))
      (node (ref "SJ1") (pin "1") (pinfunction "1_1") (pintype "passive"))
      (node (ref "SW_DN") (pin "1") (pinfunction "1_1") (pintype "passive"))
      (node (ref "SW_ENT") (pin "1") (pinfunction "1_1") (pintype "passive"))
      (node (ref "SW_UP") (pin "1") (pinfunction "1_1") (pintype "passive"))
      (node (ref "TP_BAT_GND") (pin "TP") (pinfunction "TP_TP") (pintype "input"))
      (node (ref "TP_GND") (pin "TP") (pinfunction "TP_TP") (pintype "input"))
      (node (ref "U1") (pin "P$74") (pinfunction "VSS_PAD_P$74") (pintype "bidirectional"))
      (node (ref "U1") (pin "P$75") (pinfunction "VSS_PAD_P$75") (pintype "bidirectional"))
      (node (ref "U1") (pin "P$76") (pinfunction "VSS_PAD_P$76") (pintype "bidirectional"))
      (node (ref "U1") (pin "P$77") (pinfunction "VSS_PAD_P$77") (pintype "bidirectional"))
      (node (ref "U1") (pin "P$78") (pinfunction "VSS_PAD_P$78") (pintype "bidirectional"))
      (node (ref "U1") (pin "P$79") (pinfunction "VSS_PAD_P$79") (pintype "bidirectional"))
      (node (ref "U1") (pin "P$80") (pinfunction "VSS_PAD_P$80") (pintype "bidirectional"))
      (node (ref "U1") (pin "P$81") (pinfunction "VSS_PAD_P$81") (pintype "bidirectional"))
      (node (ref "U1") (pin "P$82") (pinfunction "VSS_PAD_P$82") (pintype "bidirectional"))
      (node (ref "U1") (pin "P$83") (pinfunction "VSS_PAD_P$83") (pintype "bidirectional"))
      (node (ref "U1") (pin "P$84") (pinfunction "VSS_PAD_P$84") (pintype "bidirectional"))
      (node (ref "U1") (pin "P$85") (pinfunction "VSS_PAD_P$85") (pintype "bidirectional"))
      (node (ref "U1") (pin "P$86") (pinfunction "VSS_PAD_P$86") (pintype "bidirectional"))
      (node (ref "U1") (pin "P$87") (pinfunction "VSS_PAD_P$87") (pintype "bidirectional"))
      (node (ref "U1") (pin "P$88") (pinfunction "VSS_PAD_P$88") (pintype "bidirectional"))
      (node (ref "U1") (pin "P$89") (pinfunction "VSS_PAD_P$89") (pintype "bidirectional"))
      (node (ref "U1") (pin "P$90") (pinfunction "VSS_PAD_P$90") (pintype "bidirectional"))
      (node (ref "U1") (pin "P$B7") (pinfunction "VSS_P$B7") (pintype "power_in"))
      (node (ref "U1") (pin "P$F23") (pinfunction "VSS_PA_P$F23") (pintype "bidirectional"))
      (node (ref "U3") (pin "1") (pinfunction "CTG_1") (pintype "power_in"))
      (node (ref "U3") (pin "4") (pinfunction "GND_4") (pintype "power_in"))
      (node (ref "U3") (pin "6") (pinfunction "QSTRT_6") (pintype "input"))
      (node (ref "U3") (pin "9") (pinfunction "EP_9") (pintype "power_in"))
      (node (ref "X1") (pin "2") (pinfunction "2_2") (pintype "passive"))
      (node (ref "X1") (pin "4") (pinfunction "4_4") (pintype "passive"))
    )
    (net (code "18") (name "HAPTIC_EN") (class "Default")
      (node (ref "IC2") (pin "A1") (pinfunction "EN_A1") (pintype "bidirectional"))
      (node (ref "U1") (pin "P$U1") (pinfunction "P0.12_P$U1") (pintype "bidirectional"))
    )
    (net (code "19") (name "IMU_INT1") (class "Default")
      (node (ref "IC3") (pin "5") (pinfunction "INT1_5") (pintype "bidirectional"))
      (node (ref "U1") (pin "P$N1") (pinfunction "P0.08_P$N1") (pintype "bidirectional"))
    )
    (net (code "20") (name "IMU_INT2") (class "Default")
      (node (ref "IC3") (pin "6") (pinfunction "INT2_6") (pintype "bidirectional"))
      (node (ref "U1") (pin "P$P2") (pinfunction "P1.08_P$P2") (pintype "bidirectional"))
    )
    (net (code "21") (name "LX1") (class "Default")
      (node (ref "IC9") (pin "B2") (pinfunction "SW1_1_B2") (pintype "bidirectional"))
      (node (ref "IC9") (pin "B3") (pinfunction "SW1_2_B3") (pintype "bidirectional"))
      (node (ref "L7") (pin "1") (pinfunction "1_1") (pintype "bidirectional"))
    )
    (net (code "22") (name "LX2") (class "Default")
      (node (ref "IC9") (pin "D2") (pinfunction "SW2_1_D2") (pintype "bidirectional"))
      (node (ref "IC9") (pin "D3") (pinfunction "SW2_2_D3") (pintype "bidirectional"))
      (node (ref "L7") (pin "2") (pinfunction "2_2") (pintype "bidirectional"))
    )
    (net (code "23") (name "MOSI") (class "Default")
      (node (ref "J1") (pin "14") (pinfunction "14_14") (pintype "bidirectional"))
      (node (ref "U1") (pin "P$B13") (pinfunction "P0.03/AIN1_P$B13") (pintype "bidirectional"))
    )
    (net (code "24") (name "Net-(D2-K)") (class "Default")
      (node (ref "C2-EP-DR") (pin "1") (pinfunction "1_1") (pintype "passive"))
      (node (ref "D2") (pin "1") (pinfunction "K_1") (pintype "bidirectional"))
      (node (ref "D4") (pin "2") (pinfunction "A_2") (pintype "bidirectional"))
      (node (ref "Q3") (pin "3") (pinfunction "D_3") (pintype "bidirectional"))
    )
    (net (code "25") (name "Net-(D5-A)") (class "Default")
      (node (ref "C2-EP-DR") (pin "2") (pinfunction "2_2") (pintype "passive"))
      (node (ref "D5") (pin "2") (pinfunction "A_2") (pintype "bidirectional"))
      (node (ref "L5") (pin "1") (pinfunction "1_1") (pintype "passive"))
    )
    (net (code "26") (name "Net-(EPD_C1-Pad2)") (class "Default")
      (node (ref "EPD_C1") (pin "2") (pinfunction "2_2") (pintype "passive"))
      (node (ref "J1") (pin "5") (pinfunction "5_5") (pintype "bidirectional"))
    )
    (net (code "27") (name "Net-(EPD_C2-Pad2)") (class "Default")
      (node (ref "EPD_C2") (pin "2") (pinfunction "2_2") (pintype "passive"))
      (node (ref "J1") (pin "4") (pinfunction "4_4") (pintype "bidirectional"))
    )
    (net (code "28") (name "Net-(EPD_C6-Pad2)") (class "Default")
      (node (ref "EPD_C6") (pin "2") (pinfunction "2_2") (pintype "passive"))
      (node (ref "J1") (pin "18") (pinfunction "18_18") (pintype "bidirectional"))
    )
    (net (code "29") (name "Net-(EPD_C7-Pad2)") (class "Default")
      (node (ref "EPD_C7") (pin "2") (pinfunction "2_2") (pintype "passive"))
      (node (ref "J1") (pin "19") (pinfunction "19_19") (pintype "bidirectional"))
    )
    (net (code "30") (name "Net-(EPD_C8-Pad2)") (class "Default")
      (node (ref "EPD_C8") (pin "2") (pinfunction "2_2") (pintype "passive"))
      (node (ref "J1") (pin "20") (pinfunction "20_20") (pintype "bidirectional"))
    )
    (net (code "31") (name "Net-(EPD_C10-Pad2)") (class "Default")
      (node (ref "EPD_C10") (pin "2") (pinfunction "2_2") (pintype "passive"))
      (node (ref "J1") (pin "22") (pinfunction "22_22") (pintype "bidirectional"))
    )
    (net (code "32") (name "Net-(EPD_C12-Pad2)") (class "Default")
      (node (ref "EPD_C12") (pin "2") (pinfunction "2_2") (pintype "passive"))
      (node (ref "J1") (pin "24") (pinfunction "24_24") (pintype "bidirectional"))
    )
    (net (code "33") (name "Net-(IC1-TS{slash}MR)") (class "Default")
      (node (ref "IC1") (pin "D1") (pinfunction "TS/MR_D1") (pintype "bidirectional"))
      (node (ref "R9") (pin "2") (pinfunction "2_2") (pintype "bidirectional"))
    )
    (net (code "34") (name "Net-(IC2-REG)") (class "Default")
      (node (ref "C32") (pin "2") (pinfunction "2_2") (pintype "passive"))
      (node (ref "IC2") (pin "A2") (pinfunction "REG_A2") (pintype "bidirectional"))
    )
    (net (code "35") (name "Net-(IC3-SDO)") (class "Default")
      (node (ref "IC3") (pin "1") (pinfunction "SDO_1") (pintype "bidirectional"))
      (node (ref "R3") (pin "2") (pinfunction "2_2") (pintype "bidirectional"))
    )
    (net (code "36") (name "Net-(IC9-SCL)") (class "Default")
      (node (ref "IC9") (pin "D1") (pinfunction "SCL_D1") (pintype "bidirectional"))
      (node (ref "R4") (pin "2") (pinfunction "2_2") (pintype "bidirectional"))
    )
    (net (code "37") (name "Net-(IC9-SDA)") (class "Default")
      (node (ref "IC9") (pin "E1") (pinfunction "SDA_E1") (pintype "bidirectional"))
      (node (ref "R2") (pin "2") (pinfunction "2_2") (pintype "bidirectional"))
    )
    (net (code "38") (name "Net-(J4-CC1)") (class "Default")
      (node (ref "J4") (pin "A5") (pinfunction "CC1_A5") (pintype "bidirectional"))
      (node (ref "R1_USB") (pin "2") (pinfunction "2_2") (pintype "bidirectional"))
    )
    (net (code "39") (name "Net-(J4-CC2)") (class "Default")
      (node (ref "J4") (pin "B5") (pinfunction "CC2_B5") (pintype "bidirectional"))
      (node (ref "R2_USB") (pin "1") (pinfunction "1_1") (pintype "bidirectional"))
    )
    (net (code "40") (name "Net-(L2-Pad2)") (class "Default")
      (node (ref "L2") (pin "2") (pinfunction "2_2") (pintype "passive"))
      (node (ref "L3") (pin "1") (pinfunction "1_1") (pintype "passive"))
    )
    (net (code "41") (name "Net-(R1_EP_DR1-Pad1)") (class "Default")
      (node (ref "R1_EP_DR1") (pin "1") (pinfunction "1_1") (pintype "bidirectional"))
      (node (ref "R_TYPE_SEL") (pin "2") (pinfunction "2_2") (pintype "bidirectional"))
      (node (ref "SJ1") (pin "2") (pinfunction "2_2") (pintype "passive"))
    )
    (net (code "42") (name "Net-(U1-ANT)") (class "Default")
      (node (ref "C3") (pin "1") (pinfunction "1_1") (pintype "passive"))
      (node (ref "L1") (pin "1") (pinfunction "1_1") (pintype "passive"))
      (node (ref "U1") (pin "P$H23") (pinfunction "ANT_P$H23") (pintype "bidirectional"))
    )
    (net (code "43") (name "Net-(U1-DCC)") (class "Default")
      (node (ref "L2") (pin "1") (pinfunction "1_1") (pintype "passive"))
      (node (ref "U1") (pin "P$B3") (pinfunction "DCC_P$B3") (pintype "output"))
    )
    (net (code "44") (name "Net-(U1-DEC2)") (class "Default")
      (node (ref "C13") (pin "1") (pinfunction "1_1") (pintype "passive"))
      (node (ref "U1") (pin "P$A18") (pinfunction "DEC2_P$A18") (pintype "bidirectional"))
    )
    (net (code "45") (name "Net-(U1-DEC3V3)") (class "Default")
      (node (ref "C20") (pin "1") (pinfunction "1_1") (pintype "passive"))
      (node (ref "U1") (pin "P$AC5") (pinfunction "DEC3V3_P$AC5") (pintype "bidirectional"))
    )
    (net (code "46") (name "Net-(U1-DEC5)") (class "Default")
      (node (ref "C9") (pin "1") (pinfunction "1_1") (pintype "passive"))
      (node (ref "U1") (pin "P$N24") (pinfunction "DEC5_P$N24") (pintype "bidirectional"))
    )
    (net (code "47") (name "Net-(U1-XC1)") (class "Default")
      (node (ref "C1") (pin "1") (pinfunction "1_1") (pintype "passive"))
      (node (ref "U1") (pin "P$B24") (pinfunction "XC1_P$B24") (pintype "input"))
      (node (ref "X1") (pin "1") (pinfunction "1_1") (pintype "passive"))
    )
    (net (code "48") (name "Net-(U1-XC2)") (class "Default")
      (node (ref "C2") (pin "1") (pinfunction "1_1") (pintype "passive"))
      (node (ref "U1") (pin "P$A23") (pinfunction "XC2_P$A23") (pintype "output"))
      (node (ref "X1") (pin "3") (pinfunction "3_3") (pintype "passive"))
    )
    (net (code "49") (name "OUT+") (class "Default")
      (node (ref "IC2") (pin "A3") (pinfunction "OUT+_A3") (pintype "bidirectional"))
      (node (ref "TP_OP") (pin "TP") (pinfunction "TP_TP") (pintype "input"))
    )
    (net (code "50") (name "OUT-") (class "Default")
      (node (ref "IC2") (pin "C3") (pinfunction "OUT-_C3") (pintype "bidirectional"))
      (node (ref "TP_ON") (pin "TP") (pinfunction "TP_TP") (pintype "input"))
    )
    (net (code "51") (name "P0.01{slash}XL1") (class "Default")
      (node (ref "C17") (pin "2") (pinfunction "2_2") (pintype "passive"))
      (node (ref "U1") (pin "P$D2") (pinfunction "P0.00/XL1_P$D2") (pintype "bidirectional"))
      (node (ref "X2") (pin "1") (pinfunction "1_1") (pintype "passive"))
    )
    (net (code "52") (name "P0.01{slash}XL2") (class "Default")
      (node (ref "C18") (pin "2") (pinfunction "2_2") (pintype "passive"))
      (node (ref "U1") (pin "P$F2") (pinfunction "P0.01/XL2_P$F2") (pintype "bidirectional"))
      (node (ref "X2") (pin "2") (pinfunction "2_2") (pintype "passive"))
    )
    (net (code "53") (name "P0.04") (class "Default")
      (node (ref "U1") (pin "P$J1") (pinfunction "P0.04/AIN2_P$J1") (pintype "bidirectional"))
    )
    (net (code "54") (name "P0.09") (class "Default")
      (node (ref "U1") (pin "P$L24") (pinfunction "P0.09/NFC1_P$L24") (pintype "bidirectional"))
    )
    (net (code "55") (name "P0.13") (class "Default")
      (node (ref "C30") (pin "2") (pinfunction "2_2") (pintype "passive"))
      (node (ref "R5") (pin "1") (pinfunction "1_1") (pintype "bidirectional"))
      (node (ref "SW_UP") (pin "2") (pinfunction "2_2") (pintype "passive"))
      (node (ref "U1") (pin "P$AD8") (pinfunction "P0.13_P$AD8") (pintype "bidirectional"))
    )
    (net (code "56") (name "P0.14") (class "Default")
      (node (ref "C31") (pin "2") (pinfunction "2_2") (pintype "passive"))
      (node (ref "R8") (pin "1") (pinfunction "1_1") (pintype "bidirectional"))
      (node (ref "SW_ENT") (pin "2") (pinfunction "2_2") (pintype "passive"))
      (node (ref "U1") (pin "P$AC9") (pinfunction "P0.14_P$AC9") (pintype "bidirectional"))
    )
    (net (code "57") (name "P0.19") (class "Default")
      (node (ref "U1") (pin "P$AC15") (pinfunction "P0.19_P$AC15") (pintype "bidirectional"))
    )
    (net (code "58") (name "P0.20") (class "Default")
      (node (ref "U1") (pin "P$AD16") (pinfunction "P0.20_P$AD16") (pintype "bidirectional"))
    )
    (net (code "59") (name "P0.21") (class "Default")
      (node (ref "U1") (pin "P$AC17") (pinfunction "P0.21_P$AC17") (pintype "bidirectional"))
    )
    (net (code "60") (name "P0.22") (class "Default")
      (node (ref "U1") (pin "P$AD18") (pinfunction "P0.22_P$AD18") (pintype "bidirectional"))
    )
    (net (code "61") (name "P0.23") (class "Default")
      (node (ref "U1") (pin "P$AC19") (pinfunction "P0.23_P$AC19") (pintype "bidirectional"))
    )
    (net (code "62") (name "P0.24") (class "Default")
      (node (ref "U1") (pin "P$AD20") (pinfunction "P0.24_P$AD20") (pintype "bidirectional"))
    )
    (net (code "63") (name "P0.25") (class "Default")
      (node (ref "U1") (pin "P$AC21") (pinfunction "P0.25_P$AC21") (pintype "bidirectional"))
    )
    (net (code "64") (name "P0.26") (class "Default")
      (node (ref "U1") (pin "P$G1") (pinfunction "P0.26_P$G1") (pintype "bidirectional"))
    )
    (net (code "65") (name "P0.27") (class "Default")
      (node (ref "U1") (pin "P$H2") (pinfunction "P0.27_P$H2") (pintype "bidirectional"))
    )
    (net (code "66") (name "P0.28") (class "Default")
      (node (ref "U1") (pin "P$B11") (pinfunction "P0.28/AIN4_P$B11") (pintype "bidirectional"))
    )
    (net (code "67") (name "P0.29") (class "Default")
      (node (ref "U1") (pin "P$A10") (pinfunction "P0.29/AIN5_P$A10") (pintype "bidirectional"))
    )
    (net (code "68") (name "P0.30") (class "Default")
      (node (ref "U1") (pin "P$B9") (pinfunction "P0.30/AIN6_P$B9") (pintype "bidirectional"))
    )
    (net (code "69") (name "P0.31") (class "Default")
      (node (ref "U1") (pin "P$A8") (pinfunction "P0.31/AIN7_P$A8") (pintype "bidirectional"))
    )
    (net (code "70") (name "P1.01") (class "Default")
      (node (ref "DMG2305UX-7") (pin "1") (pinfunction "G_1") (pintype "bidirectional"))
      (node (ref "R_PWR_EPD") (pin "1") (pinfunction "1_1") (pintype "bidirectional"))
      (node (ref "U1") (pin "P$Y23") (pinfunction "P1.01_P$Y23") (pintype "bidirectional"))
    )
    (net (code "71") (name "P1.02") (class "Default")
      (node (ref "C29") (pin "2") (pinfunction "2_2") (pintype "passive"))
      (node (ref "R7") (pin "1") (pinfunction "1_1") (pintype "bidirectional"))
      (node (ref "SW_DN") (pin "2") (pinfunction "2_2") (pintype "passive"))
      (node (ref "U1") (pin "P$W24") (pinfunction "P1.02_P$W24") (pintype "bidirectional"))
    )
    (net (code "72") (name "P1.03") (class "Default")
      (node (ref "U1") (pin "P$V23") (pinfunction "P1.03_P$V23") (pintype "bidirectional"))
    )
    (net (code "73") (name "P1.04") (class "Default")
      (node (ref "U1") (pin "P$U24") (pinfunction "P1.04_P$U24") (pintype "bidirectional"))
    )
    (net (code "74") (name "P1.05") (class "Default")
      (node (ref "U1") (pin "P$T23") (pinfunction "P1.05_P$T23") (pintype "bidirectional"))
    )
    (net (code "75") (name "P1.06") (class "Default")
      (node (ref "U1") (pin "P$R24") (pinfunction "P1.06_P$R24") (pintype "bidirectional"))
    )
    (net (code "76") (name "P1.07") (class "Default")
      (node (ref "U1") (pin "P$P23") (pinfunction "P1.07_P$P23") (pintype "bidirectional"))
    )
    (net (code "77") (name "P1.09") (class "Default")
      (node (ref "U1") (pin "P$R1") (pinfunction "P1.09_P$R1") (pintype "bidirectional"))
    )
    (net (code "78") (name "P1.10") (class "Default")
      (node (ref "U1") (pin "P$A20") (pinfunction "P1.10_P$A20") (pintype "bidirectional"))
    )
    (net (code "79") (name "P1.11") (class "Default")
      (node (ref "U1") (pin "P$B19") (pinfunction "P1.11_P$B19") (pintype "bidirectional"))
    )
    (net (code "80") (name "P1.12") (class "Default")
      (node (ref "U1") (pin "P$B17") (pinfunction "P1.12_P$B17") (pintype "bidirectional"))
    )
    (net (code "81") (name "P1.13") (class "Default")
      (node (ref "U1") (pin "P$A16") (pinfunction "P1.13_P$A16") (pintype "bidirectional"))
    )
    (net (code "82") (name "P1.14") (class "Default")
      (node (ref "U1") (pin "P$B15") (pinfunction "P1.14_P$B15") (pintype "bidirectional"))
    )
    (net (code "83") (name "P1.15") (class "Default")
      (node (ref "U1") (pin "P$A14") (pinfunction "P1.15_P$A14") (pintype "bidirectional"))
    )
    (net (code "84") (name "PMIC_INT") (class "Default")
      (node (ref "IC1") (pin "A1") (pinfunction "~{INT}_A1") (pintype "bidirectional"))
      (node (ref "U1") (pin "P$T2") (pinfunction "P0.11_P$T2") (pintype "bidirectional"))
    )
    (net (code "85") (name "PREVGH") (class "Default")
      (node (ref "D5") (pin "1") (pinfunction "K_1") (pintype "bidirectional"))
      (node (ref "EPD_C9") (pin "2") (pinfunction "2_2") (pintype "passive"))
      (node (ref "J1") (pin "21") (pinfunction "21_21") (pintype "bidirectional"))
    )
    (net (code "86") (name "PREVGL") (class "Default")
      (node (ref "D2") (pin "2") (pinfunction "A_2") (pintype "bidirectional"))
      (node (ref "EPD_C11") (pin "2") (pinfunction "2_2") (pintype "passive"))
      (node (ref "J1") (pin "23") (pinfunction "23_23") (pintype "bidirectional"))
    )
    (net (code "87") (name "RESE") (class "Default")
      (node (ref "J1") (pin "3") (pinfunction "3_3") (pintype "bidirectional"))
      (node (ref "Q3") (pin "2") (pinfunction "S_2") (pintype "bidirectional"))
      (node (ref "R1_EP_DR1") (pin "2") (pinfunction "2_2") (pintype "bidirectional"))
    )
    (net (code "88") (name "RESET") (class "Default")
      (node (ref "J2") (pin "6") (pinfunction "6_6") (pintype "bidirectional"))
      (node (ref "TP_RESET") (pin "TP") (pinfunction "TP_TP") (pintype "input"))
      (node (ref "U1") (pin "P$AC13") (pinfunction "P0.18/RESET_P$AC13") (pintype "bidirectional"))
    )
    (net (code "89") (name "RF") (class "Default")
      (node (ref "ANT1") (pin "1") (pinfunction "FEED_1") (pintype "input"))
      (node (ref "C22") (pin "1") (pinfunction "1_1") (pintype "passive"))
      (node (ref "C4") (pin "1") (pinfunction "1_1") (pintype "passive"))
      (node (ref "L1") (pin "2") (pinfunction "2_2") (pintype "passive"))
    )
    (net (code "90") (name "SCK") (class "Default")
      (node (ref "J1") (pin "13") (pinfunction "13_13") (pintype "bidirectional"))
      (node (ref "U1") (pin "P$A12") (pinfunction "P0.02/AIN0_P$A12") (pintype "bidirectional"))
    )
    (net (code "91") (name "SCL") (class "Default")
      (node (ref "IC1") (pin "B1") (pinfunction "SCL_B1") (pintype "bidirectional"))
      (node (ref "IC2") (pin "C1") (pinfunction "SCL_C1") (pintype "bidirectional"))
      (node (ref "IC3") (pin "12") (pinfunction "SCX_12") (pintype "bidirectional"))
      (node (ref "R17") (pin "1") (pinfunction "1_1") (pintype "bidirectional"))
      (node (ref "R4") (pin "1") (pinfunction "1_1") (pintype "bidirectional"))
      (node (ref "TP_SCL") (pin "TP") (pinfunction "TP_TP") (pintype "input"))
      (node (ref "U1") (pin "P$M2") (pinfunction "P0.07_P$M2") (pintype "bidirectional"))
      (node (ref "U3") (pin "7") (pinfunction "SCL_7") (pintype "input"))
    )
    (net (code "92") (name "SDA") (class "Default")
      (node (ref "IC1") (pin "C1") (pinfunction "SDA_C1") (pintype "bidirectional"))
      (node (ref "IC2") (pin "B2") (pinfunction "SDA_B2") (pintype "bidirectional"))
      (node (ref "IC3") (pin "2") (pinfunction "SDX_2") (pintype "bidirectional"))
      (node (ref "R18") (pin "1") (pinfunction "1_1") (pintype "bidirectional"))
      (node (ref "R2") (pin "1") (pinfunction "1_1") (pintype "bidirectional"))
      (node (ref "TP_SDA") (pin "TP") (pinfunction "TP_TP") (pintype "input"))
      (node (ref "U1") (pin "P$L1") (pinfunction "P0.06_P$L1") (pintype "bidirectional"))
      (node (ref "U3") (pin "8") (pinfunction "SDA_8") (pintype "bidirectional"))
    )
    (net (code "93") (name "SWDCLK") (class "Default")
      (node (ref "J2") (pin "4") (pinfunction "4_4") (pintype "bidirectional"))
      (node (ref "TP_SWDCLK") (pin "TP") (pinfunction "TP_TP") (pintype "input"))
      (node (ref "U1") (pin "P$AA24") (pinfunction "SWDCLK_P$AA24") (pintype "input"))
    )
    (net (code "94") (name "SWDIO") (class "Default")
      (node (ref "J2") (pin "2") (pinfunction "2_2") (pintype "bidirectional"))
      (node (ref "TP_SWDIO") (pin "TP") (pinfunction "TP_TP") (pintype "input"))
      (node (ref "U1") (pin "P$AC24") (pinfunction "SWDIO_P$AC24") (pintype "bidirectional"))
    )
    (net (code "95") (name "SWO") (class "Default")
      (node (ref "TP_SWO") (pin "TP") (pinfunction "TP_TP") (pintype "input"))
      (node (ref "U1") (pin "P$AD22") (pinfunction "P1.00_P$AD22") (pintype "bidirectional"))
    )
    (net (code "96") (name "VBAT") (class "Default")
      (node (ref "C27") (pin "2") (pinfunction "2_2") (pintype "passive"))
      (node (ref "C37") (pin "2") (pinfunction "2_2") (pintype "passive"))
      (node (ref "IC1") (pin "C2") (pinfunction "BAT_C2") (pintype "bidirectional"))
      (node (ref "TP_VBAT") (pin "TP") (pinfunction "TP_TP") (pintype "input"))
      (node (ref "U3") (pin "2") (pinfunction "CELL_2") (pintype "power_in"))
      (node (ref "U3") (pin "3") (pinfunction "VDD_3") (pintype "power_in"))
    )
    (net (code "97") (name "VBUS") (class "Default")
      (node (ref "C21") (pin "1") (pinfunction "1_1") (pintype "passive"))
      (node (ref "C38") (pin "2") (pinfunction "2_2") (pintype "passive"))
      (node (ref "C42") (pin "1") (pinfunction "1_1") (pintype "passive"))
      (node (ref "C43") (pin "1") (pinfunction "1_1") (pintype "passive"))
      (node (ref "D3") (pin "5") (pinfunction "VBUS_5") (pintype "bidirectional"))
      (node (ref "IC1") (pin "A2") (pinfunction "IN_A2") (pintype "bidirectional"))
      (node (ref "J4") (pin "A4_B9") (pinfunction "VBUS_A4_B9") (pintype "power_in"))
      (node (ref "J4") (pin "A9_B4") (pinfunction "VBUS_A9_B4") (pintype "power_in"))
      (node (ref "U1") (pin "P$AD2") (pinfunction "VBUS_P$AD2") (pintype "power_in"))
    )
    (net (code "98") (name "VREG") (class "Default")
      (node (ref "C23") (pin "2") (pinfunction "2_2") (pintype "passive"))
      (node (ref "C24") (pin "2") (pinfunction "2_2") (pintype "passive"))
      (node (ref "C39") (pin "1") (pinfunction "1_1") (pintype "passive"))
      (node (ref "IC1") (pin "B2") (pinfunction "SYS_B2") (pintype "bidirectional"))
      (node (ref "IC9") (pin "A1") (pinfunction "EN_A1") (pintype "bidirectional"))
      (node (ref "IC9") (pin "A2") (pinfunction "VIN_1_A2") (pintype "bidirectional"))
      (node (ref "IC9") (pin "A3") (pinfunction "VIN_2_A3") (pintype "bidirectional"))
      (node (ref "TP_VREG") (pin "TP") (pinfunction "TP_TP") (pintype "input"))
    )
    (net (code "99") (name "unconnected-(ANT1-NC-Pad2)") (class "Default")
      (node (ref "ANT1") (pin "2") (pinfunction "NC_2") (pintype "no_connect"))
    )
    (net (code "100") (name "unconnected-(IC3-ASCL-Pad11)") (class "Default")
      (node (ref "IC3") (pin "11") (pinfunction "ASCL_11") (pintype "bidirectional"))
    )
    (net (code "101") (name "unconnected-(IC3-ASDA-Pad4)") (class "Default")
      (node (ref "IC3") (pin "4") (pinfunction "ASDA_4") (pintype "bidirectional"))
    )
    (net (code "102") (name "unconnected-(J1-Pad1)") (class "Default")
      (node (ref "J1") (pin "1") (pinfunction "1_1") (pintype "bidirectional"))
    )
    (net (code "103") (name "unconnected-(J1-Pad6)") (class "Default")
      (node (ref "J1") (pin "6") (pinfunction "6_6") (pintype "bidirectional"))
    )
    (net (code "104") (name "unconnected-(J1-Pad7)") (class "Default")
      (node (ref "J1") (pin "7") (pinfunction "7_7") (pintype "bidirectional"))
    )
    (net (code "105") (name "unconnected-(J4-SBU1-PadA8)") (class "Default")
      (node (ref "J4") (pin "A8") (pinfunction "SBU1_A8") (pintype "bidirectional"))
    )
    (net (code "106") (name "unconnected-(J4-SBU2-PadB8)") (class "Default")
      (node (ref "J4") (pin "B8") (pinfunction "SBU2_B8") (pintype "bidirectional"))
    )
    (net (code "107") (name "unconnected-(U1-DCCH-PadP$AB2)") (class "Default")
      (node (ref "U1") (pin "P$AB2") (pinfunction "DCCH_P$AB2") (pintype "bidirectional"))
    )
  )
)
